# ESP32_VGA_Pocket.net
KiCad netlist of a schematic drawn in EAGLE
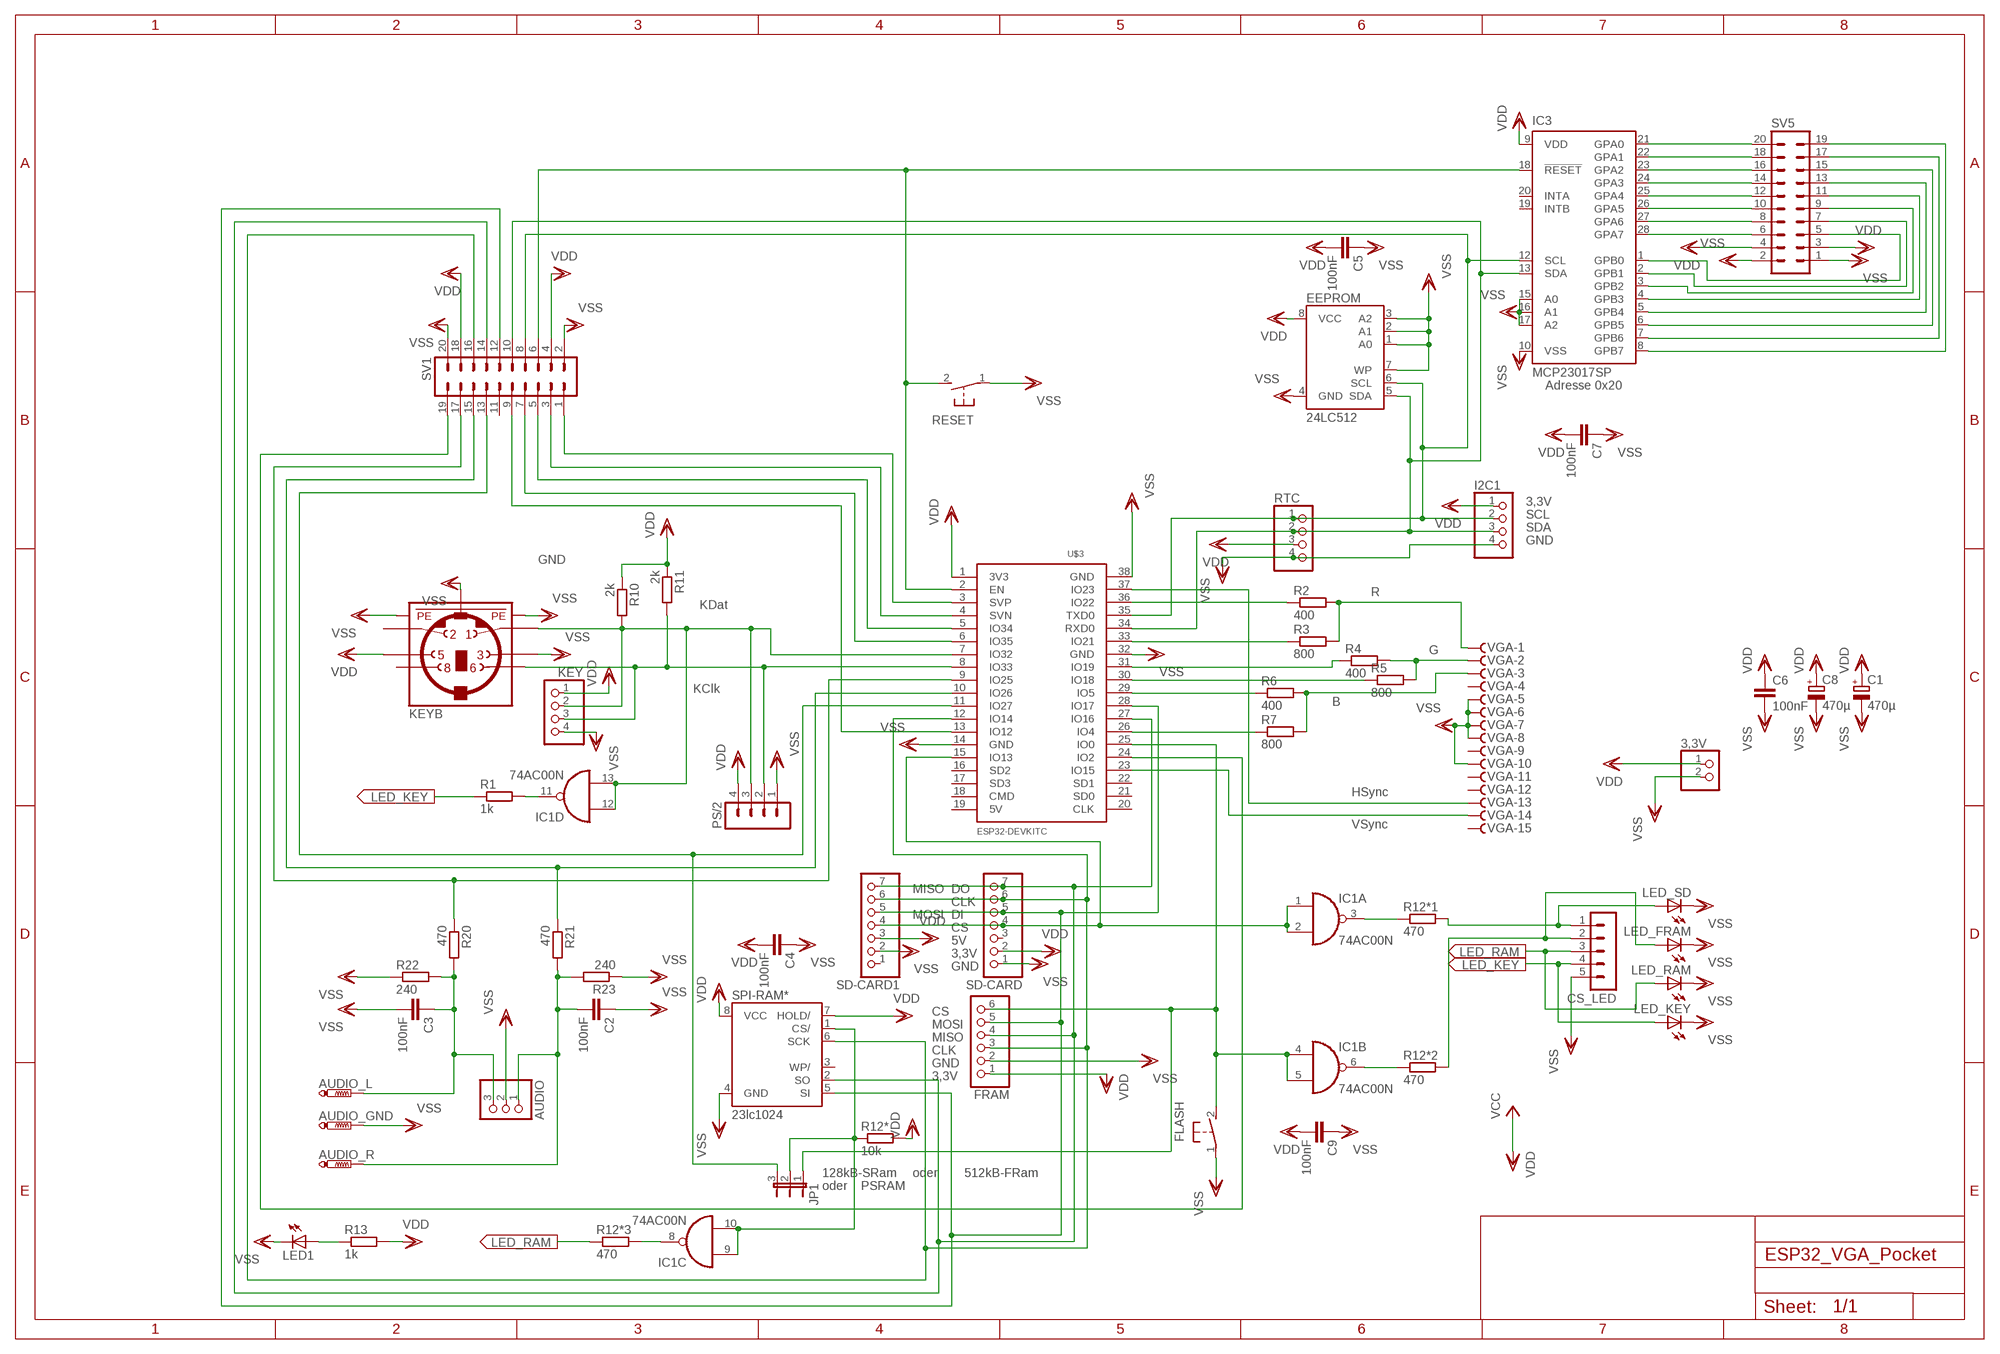
[diagram p0: schematic, sheet 1]

(export (version "E")
  (design (tool "Eeschema 10.0.6"))
  (components
    (comp (ref "3,3V")
      (value "PINHD-1X2")
      (footprint "eagle-import:1X02")
      (libsource (lib "eagle-import") (part "PINHD-1X2"))
    )
    (comp (ref "AUDIO")
      (value "PINHD-1X3")
      (footprint "eagle-import:1X03")
      (libsource (lib "eagle-import") (part "PINHD-1X3"))
    )
    (comp (ref "AUDIO_GND")
      (value "PTR1PAD1-13Y")
      (footprint "eagle-import:P1-13Y")
      (libsource (lib "eagle-import") (part "PTR1PAD1-13Y"))
    )
    (comp (ref "AUDIO_L")
      (value "PTR1PAD1-13Y")
      (footprint "eagle-import:P1-13Y")
      (libsource (lib "eagle-import") (part "PTR1PAD1-13Y"))
    )
    (comp (ref "AUDIO_R")
      (value "PTR1PAD1-13Y")
      (footprint "eagle-import:P1-13Y")
      (libsource (lib "eagle-import") (part "PTR1PAD1-13Y"))
    )
    (comp (ref "C1")
      (value "470µ")
      (footprint "eagle-import:E3,5-10")
      (libsource (lib "eagle-import") (part "CPOL-EUE3.5-10"))
    )
    (comp (ref "C2")
      (value "100nF")
      (footprint "eagle-import:C025-030X050")
      (libsource (lib "eagle-import") (part "C-EU025-030X050"))
    )
    (comp (ref "C3")
      (value "100nF")
      (footprint "eagle-import:C025-030X050")
      (libsource (lib "eagle-import") (part "C-EU025-030X050"))
    )
    (comp (ref "C4")
      (value "100nF")
      (footprint "eagle-import:C025-030X050")
      (libsource (lib "eagle-import") (part "C-EU025-030X050"))
    )
    (comp (ref "C5")
      (value "100nF")
      (footprint "eagle-import:C025-030X050")
      (libsource (lib "eagle-import") (part "C-EU025-030X050"))
    )
    (comp (ref "C6")
      (value "100nF")
      (footprint "eagle-import:C025-030X050")
      (libsource (lib "eagle-import") (part "C-EU025-030X050"))
    )
    (comp (ref "C7")
      (value "100nF")
      (footprint "eagle-import:C025-030X050")
      (libsource (lib "eagle-import") (part "C-EU025-030X050"))
    )
    (comp (ref "C8")
      (value "470µ")
      (footprint "eagle-import:E3,5-10")
      (libsource (lib "eagle-import") (part "CPOL-EUE3.5-10"))
    )
    (comp (ref "C9")
      (value "100nF")
      (footprint "eagle-import:C025-030X050")
      (libsource (lib "eagle-import") (part "C-EU025-030X050"))
    )
    (comp (ref "CS_LED")
      (value "MA05-1")
      (footprint "eagle-import:MA05-1")
      (libsource (lib "eagle-import") (part "MA05-1"))
    )
    (comp (ref "EEPROM")
      (value "24LC512")
      (footprint "eagle-import:DIL08")
      (fields (field (name "MPN") "AT24C1024BW-SH-B"))
      (libsource (lib "eagle-import") (part "AT24CP"))
    )
    (comp (ref "FLASH")
      (value "31-XX")
      (footprint "eagle-import:B3F-31XX")
      (fields
        (field (name "MPN") "B3F-3100")
        (field (name "MPN_1") "B3F-3100")
        (field (name "OC_FARNELL") "959704")
        (field (name "OC_NEWARK") "36M3582")
      )
      (libsource (lib "eagle-import") (part "31-XX"))
    )
    (comp (ref "FRAM")
      (value "PINHD-1X6")
      (footprint "eagle-import:1X06")
      (libsource (lib "eagle-import") (part "PINHD-1X6"))
    )
    (comp (ref "I2C1")
      (value "PINHD-1X4")
      (footprint "eagle-import:1X04")
      (libsource (lib "eagle-import") (part "PINHD-1X4"))
    )
    (comp (ref "IC1")
      (value "74AC00N")
      (footprint "eagle-import:DIL14")
      (libsource (lib "eagle-import") (part "7400NAC"))
    )
    (comp (ref "IC3")
      (value "MCP23017SP")
      (footprint "eagle-import:DIL28-3")
      (fields
        (field (name "MF") "MICROCHIP")
        (field (name "MPN") "MCP23017-E/SP")
        (field (name "MPN_1") "MCP23017-E/SO")
        (field (name "OC_FARNELL") "1332087")
        (field (name "OC_NEWARK") "31K2958")
      )
      (libsource (lib "eagle-import") (part "MCP23017SP"))
    )
    (comp (ref "JP1")
      (value "JP2E")
      (footprint "eagle-import:JP2")
      (libsource (lib "eagle-import") (part "JP2E"))
    )
    (comp (ref "KEY")
      (value "PINHD-1X4")
      (footprint "eagle-import:1X04")
      (libsource (lib "eagle-import") (part "PINHD-1X4"))
    )
    (comp (ref "KEYB")
      (value "MINI_DIN_6")
      (footprint "eagle-import:M_DIN6")
      (libsource (lib "eagle-import") (part "MINI_DIN_6"))
    )
    (comp (ref "LED1")
      (value "LED5MM")
      (footprint "eagle-import:LED5MM")
      (libsource (lib "eagle-import") (part "LED5MM"))
    )
    (comp (ref "LED_FRAM")
      (value "LED5MM")
      (footprint "eagle-import:LED5MM")
      (libsource (lib "eagle-import") (part "LED5MM"))
    )
    (comp (ref "LED_KEY")
      (value "LED5MM")
      (footprint "eagle-import:LED5MM")
      (libsource (lib "eagle-import") (part "LED5MM"))
    )
    (comp (ref "LED_RAM")
      (value "LED5MM")
      (footprint "eagle-import:LED5MM")
      (libsource (lib "eagle-import") (part "LED5MM"))
    )
    (comp (ref "LED_SD")
      (value "LED5MM")
      (footprint "eagle-import:LED5MM")
      (libsource (lib "eagle-import") (part "LED5MM"))
    )
    (comp (ref "PS/2")
      (value "MA04-1")
      (footprint "eagle-import:MA04-1")
      (libsource (lib "eagle-import") (part "MA04-1"))
    )
    (comp (ref "R1")
      (value "1k")
      (footprint "eagle-import:0204_7")
      (libsource (lib "eagle-import") (part "R-EU_0204/7"))
    )
    (comp (ref "R2")
      (value "400")
      (footprint "eagle-import:0204_7")
      (libsource (lib "eagle-import") (part "R-EU_0204/7"))
    )
    (comp (ref "R3")
      (value "800")
      (footprint "eagle-import:0204_7")
      (libsource (lib "eagle-import") (part "R-EU_0204/7"))
    )
    (comp (ref "R4")
      (value "400")
      (footprint "eagle-import:0204_7")
      (libsource (lib "eagle-import") (part "R-EU_0204/7"))
    )
    (comp (ref "R5")
      (value "800")
      (footprint "eagle-import:0204_7")
      (libsource (lib "eagle-import") (part "R-EU_0204/7"))
    )
    (comp (ref "R6")
      (value "400")
      (footprint "eagle-import:0204_7")
      (libsource (lib "eagle-import") (part "R-EU_0204/7"))
    )
    (comp (ref "R7")
      (value "800")
      (footprint "eagle-import:0204_7")
      (libsource (lib "eagle-import") (part "R-EU_0204/7"))
    )
    (comp (ref "R10")
      (value "2k")
      (footprint "eagle-import:0204_7")
      (libsource (lib "eagle-import") (part "R-EU_0204/7"))
    )
    (comp (ref "R11")
      (value "2k")
      (footprint "eagle-import:0204_7")
      (libsource (lib "eagle-import") (part "R-EU_0204/7"))
    )
    (comp (ref "R12*")
      (value "10k")
      (footprint "eagle-import:0204_7")
      (libsource (lib "eagle-import") (part "R-EU_0204/7"))
    )
    (comp (ref "R12*1")
      (value "470")
      (footprint "eagle-import:0204_7")
      (libsource (lib "eagle-import") (part "R-EU_0204/7"))
    )
    (comp (ref "R12*2")
      (value "470")
      (footprint "eagle-import:0204_7")
      (libsource (lib "eagle-import") (part "R-EU_0204/7"))
    )
    (comp (ref "R12*3")
      (value "470")
      (footprint "eagle-import:0204_7")
      (libsource (lib "eagle-import") (part "R-EU_0204/7"))
    )
    (comp (ref "R13")
      (value "1k")
      (footprint "eagle-import:0204_7")
      (libsource (lib "eagle-import") (part "R-EU_0204/7"))
    )
    (comp (ref "R20")
      (value "470")
      (footprint "eagle-import:0204_7")
      (libsource (lib "eagle-import") (part "R-EU_0204/7"))
    )
    (comp (ref "R21")
      (value "470")
      (footprint "eagle-import:0204_7")
      (libsource (lib "eagle-import") (part "R-EU_0204/7"))
    )
    (comp (ref "R22")
      (value "240")
      (footprint "eagle-import:0204_7")
      (libsource (lib "eagle-import") (part "R-EU_0204/7"))
    )
    (comp (ref "R23")
      (value "240")
      (footprint "eagle-import:0204_7")
      (libsource (lib "eagle-import") (part "R-EU_0204/7"))
    )
    (comp (ref "RESET")
      (value "31-XX")
      (footprint "eagle-import:B3F-31XX")
      (fields (field (name "MPN") "B3F-3100"))
      (libsource (lib "eagle-import") (part "31-XX"))
    )
    (comp (ref "RTC")
      (value "PINHD-1X4")
      (footprint "eagle-import:1X04")
      (libsource (lib "eagle-import") (part "PINHD-1X4"))
    )
    (comp (ref "SD-CARD")
      (value "PINHD-1X7")
      (footprint "eagle-import:1X07")
      (libsource (lib "eagle-import") (part "PINHD-1X7"))
    )
    (comp (ref "SD-CARD1")
      (value "PINHD-1X7")
      (footprint "eagle-import:1X07")
      (libsource (lib "eagle-import") (part "PINHD-1X7"))
    )
    (comp (ref "SPI-RAM*")
      (value "23lc1024")
      (footprint "eagle-import:DIL08")
      (fields (field (name "MPN") "CAT25040LI-G"))
      (libsource (lib "eagle-import") (part "AT25P"))
    )
    (comp (ref "SV1")
      (value "MA10-2")
      (footprint "eagle-import:MA10-2")
      (libsource (lib "eagle-import") (part "MA10-2"))
    )
    (comp (ref "SV5")
      (value "MA10-2")
      (footprint "eagle-import:MA10-2")
      (libsource (lib "eagle-import") (part "MA10-2"))
    )
    (comp (ref "U$3")
      (value "ESP32DEVKITC")
      (footprint "eagle-import:ESP32-DEVKITC")
      (libsource (lib "eagle-import") (part "ESP32DEVKITC"))
    )
    (comp (ref "VGA")
      (value "F15HDHS")
      (footprint "eagle-import:HDF15H")
      (libsource (lib "eagle-import") (part "F15?SHDH"))
    )
  )
  (nets
    (net (code "1") (name "/LED_KEY") (class "Default")
      (node (ref "CS_LED") (pin "4") (pinfunction "4_4") (pintype "passive"))
      (node (ref "LED_KEY") (pin "A") (pinfunction "A_A") (pintype "passive"))
      (node (ref "R1") (pin "1") (pinfunction "1_1") (pintype "passive"))
    )
    (net (code "2") (name "/LED_RAM") (class "Default")
      (node (ref "CS_LED") (pin "3") (pinfunction "3_3") (pintype "passive"))
      (node (ref "LED_RAM") (pin "A") (pinfunction "A_A") (pintype "passive"))
      (node (ref "R12*3") (pin "1") (pinfunction "1_1") (pintype "passive"))
    )
    (net (code "3") (name "Net-(AUDIO-Pad1)") (class "Default")
      (node (ref "AUDIO") (pin "1") (pinfunction "1_1") (pintype "passive"))
      (node (ref "AUDIO_R") (pin "TP") (pinfunction "TP_TP") (pintype "input"))
      (node (ref "C2") (pin "2") (pinfunction "2_2") (pintype "passive"))
      (node (ref "R21") (pin "2") (pinfunction "2_2") (pintype "passive"))
      (node (ref "R23") (pin "2") (pinfunction "2_2") (pintype "passive"))
    )
    (net (code "4") (name "Net-(AUDIO-Pad3)") (class "Default")
      (node (ref "AUDIO") (pin "3") (pinfunction "3_3") (pintype "passive"))
      (node (ref "AUDIO_L") (pin "TP") (pinfunction "TP_TP") (pintype "input"))
      (node (ref "C3") (pin "1") (pinfunction "1_1") (pintype "passive"))
      (node (ref "R20") (pin "2") (pinfunction "2_2") (pintype "passive"))
      (node (ref "R22") (pin "2") (pinfunction "2_2") (pintype "passive"))
    )
    (net (code "5") (name "Net-(CS_LED-Pad1)") (class "Default")
      (node (ref "CS_LED") (pin "1") (pinfunction "1_1") (pintype "passive"))
      (node (ref "LED_SD") (pin "A") (pinfunction "A_A") (pintype "passive"))
      (node (ref "R12*1") (pin "2") (pinfunction "2_2") (pintype "passive"))
    )
    (net (code "6") (name "Net-(CS_LED-Pad2)") (class "Default")
      (node (ref "CS_LED") (pin "2") (pinfunction "2_2") (pintype "passive"))
      (node (ref "LED_FRAM") (pin "A") (pinfunction "A_A") (pintype "passive"))
      (node (ref "R12*2") (pin "2") (pinfunction "2_2") (pintype "passive"))
    )
    (net (code "7") (name "Net-(EEPROM-SCL)") (class "Default")
      (node (ref "EEPROM") (pin "6") (pinfunction "SCL_6") (pintype "bidirectional"))
      (node (ref "I2C1") (pin "2") (pinfunction "2_2") (pintype "passive"))
      (node (ref "IC3") (pin "12") (pinfunction "SCL_12") (pintype "input"))
      (node (ref "RTC") (pin "1") (pinfunction "1_1") (pintype "passive"))
      (node (ref "SV1") (pin "8") (pinfunction "8_8") (pintype "passive"))
      (node (ref "U$3") (pin "35") (pinfunction "TXD0_35") (pintype "bidirectional"))
    )
    (net (code "8") (name "Net-(EEPROM-SDA)") (class "Default")
      (node (ref "EEPROM") (pin "5") (pinfunction "SDA_5") (pintype "bidirectional"))
      (node (ref "I2C1") (pin "3") (pinfunction "3_3") (pintype "passive"))
      (node (ref "IC3") (pin "13") (pinfunction "SDA_13") (pintype "bidirectional"))
      (node (ref "RTC") (pin "2") (pinfunction "2_2") (pintype "passive"))
      (node (ref "SV1") (pin "10") (pinfunction "10_10") (pintype "passive"))
      (node (ref "U$3") (pin "34") (pinfunction "RXD0_34") (pintype "bidirectional"))
    )
    (net (code "9") (name "Net-(FLASH-S)") (class "Default")
      (node (ref "FLASH") (pin "2") (pinfunction "S_2") (pintype "passive"))
      (node (ref "FRAM") (pin "6") (pinfunction "6_6") (pintype "passive"))
      (node (ref "IC1") (pin "4") (pinfunction "I0_4") (pintype "input"))
      (node (ref "IC1") (pin "5") (pinfunction "I1_5") (pintype "input"))
      (node (ref "JP1") (pin "1") (pinfunction "1_1") (pintype "passive"))
      (node (ref "U$3") (pin "25") (pinfunction "IO0_25") (pintype "bidirectional"))
    )
    (net (code "10") (name "Net-(IC1A-I0)") (class "Default")
      (node (ref "IC1") (pin "1") (pinfunction "I0_1") (pintype "input"))
      (node (ref "IC1") (pin "2") (pinfunction "I1_2") (pintype "input"))
      (node (ref "SD-CARD") (pin "4") (pinfunction "4_4") (pintype "passive"))
      (node (ref "SD-CARD1") (pin "4") (pinfunction "4_4") (pintype "passive"))
      (node (ref "U$3") (pin "15") (pinfunction "IO13_15") (pintype "bidirectional"))
    )
    (net (code "11") (name "Net-(IC1A-O)") (class "Default")
      (node (ref "IC1") (pin "3") (pinfunction "O_3") (pintype "output"))
      (node (ref "R12*1") (pin "1") (pinfunction "1_1") (pintype "passive"))
    )
    (net (code "12") (name "Net-(IC1B-O)") (class "Default")
      (node (ref "IC1") (pin "6") (pinfunction "O_6") (pintype "output"))
      (node (ref "R12*2") (pin "1") (pinfunction "1_1") (pintype "passive"))
    )
    (net (code "13") (name "Net-(IC1C-I0)") (class "Default")
      (node (ref "IC1") (pin "10") (pinfunction "I1_10") (pintype "input"))
      (node (ref "IC1") (pin "9") (pinfunction "I0_9") (pintype "input"))
      (node (ref "JP1") (pin "2") (pinfunction "2_2") (pintype "passive"))
      (node (ref "R12*") (pin "1") (pinfunction "1_1") (pintype "passive"))
      (node (ref "SPI-RAM*") (pin "1") (pinfunction "CS/_1") (pintype "input"))
    )
    (net (code "14") (name "Net-(IC1C-O)") (class "Default")
      (node (ref "IC1") (pin "8") (pinfunction "O_8") (pintype "output"))
      (node (ref "R12*3") (pin "2") (pinfunction "2_2") (pintype "passive"))
    )
    (net (code "15") (name "Net-(IC1D-I0)") (class "Default")
      (node (ref "IC1") (pin "12") (pinfunction "I0_12") (pintype "input"))
      (node (ref "IC1") (pin "13") (pinfunction "I1_13") (pintype "input"))
      (node (ref "KEY") (pin "2") (pinfunction "2_2") (pintype "passive"))
      (node (ref "KEYB") (pin "1") (pinfunction "1_1") (pintype "passive"))
      (node (ref "PS/2") (pin "3") (pinfunction "3_3") (pintype "passive"))
      (node (ref "R10") (pin "2") (pinfunction "2_2") (pintype "passive"))
      (node (ref "U$3") (pin "7") (pinfunction "IO32_7") (pintype "bidirectional"))
    )
    (net (code "16") (name "Net-(IC1D-O)") (class "Default")
      (node (ref "IC1") (pin "11") (pinfunction "O_11") (pintype "output"))
      (node (ref "R1") (pin "2") (pinfunction "2_2") (pintype "passive"))
    )
    (net (code "17") (name "Net-(IC3-GPA0)") (class "Default")
      (node (ref "IC3") (pin "21") (pinfunction "GPA0_21") (pintype "bidirectional"))
      (node (ref "SV5") (pin "20") (pinfunction "20_20") (pintype "passive"))
    )
    (net (code "18") (name "Net-(IC3-GPA1)") (class "Default")
      (node (ref "IC3") (pin "22") (pinfunction "GPA1_22") (pintype "bidirectional"))
      (node (ref "SV5") (pin "18") (pinfunction "18_18") (pintype "passive"))
    )
    (net (code "19") (name "Net-(IC3-GPA2)") (class "Default")
      (node (ref "IC3") (pin "23") (pinfunction "GPA2_23") (pintype "bidirectional"))
      (node (ref "SV5") (pin "16") (pinfunction "16_16") (pintype "passive"))
    )
    (net (code "20") (name "Net-(IC3-GPA3)") (class "Default")
      (node (ref "IC3") (pin "24") (pinfunction "GPA3_24") (pintype "bidirectional"))
      (node (ref "SV5") (pin "14") (pinfunction "14_14") (pintype "passive"))
    )
    (net (code "21") (name "Net-(IC3-GPA4)") (class "Default")
      (node (ref "IC3") (pin "25") (pinfunction "GPA4_25") (pintype "bidirectional"))
      (node (ref "SV5") (pin "12") (pinfunction "12_12") (pintype "passive"))
    )
    (net (code "22") (name "Net-(IC3-GPA5)") (class "Default")
      (node (ref "IC3") (pin "26") (pinfunction "GPA5_26") (pintype "bidirectional"))
      (node (ref "SV5") (pin "10") (pinfunction "10_10") (pintype "passive"))
    )
    (net (code "23") (name "Net-(IC3-GPA6)") (class "Default")
      (node (ref "IC3") (pin "27") (pinfunction "GPA6_27") (pintype "bidirectional"))
      (node (ref "SV5") (pin "8") (pinfunction "8_8") (pintype "passive"))
    )
    (net (code "24") (name "Net-(IC3-GPA7)") (class "Default")
      (node (ref "IC3") (pin "28") (pinfunction "GPA7_28") (pintype "bidirectional"))
      (node (ref "SV5") (pin "6") (pinfunction "6_6") (pintype "passive"))
    )
    (net (code "25") (name "Net-(IC3-GPB0)") (class "Default")
      (node (ref "IC3") (pin "1") (pinfunction "GPB0_1") (pintype "bidirectional"))
      (node (ref "SV5") (pin "5") (pinfunction "5_5") (pintype "passive"))
    )
    (net (code "26") (name "Net-(IC3-GPB1)") (class "Default")
      (node (ref "IC3") (pin "2") (pinfunction "GPB1_2") (pintype "bidirectional"))
      (node (ref "SV5") (pin "7") (pinfunction "7_7") (pintype "passive"))
    )
    (net (code "27") (name "Net-(IC3-GPB2)") (class "Default")
      (node (ref "IC3") (pin "3") (pinfunction "GPB2_3") (pintype "bidirectional"))
      (node (ref "SV5") (pin "9") (pinfunction "9_9") (pintype "passive"))
    )
    (net (code "28") (name "Net-(IC3-GPB3)") (class "Default")
      (node (ref "IC3") (pin "4") (pinfunction "GPB3_4") (pintype "bidirectional"))
      (node (ref "SV5") (pin "11") (pinfunction "11_11") (pintype "passive"))
    )
    (net (code "29") (name "Net-(IC3-GPB4)") (class "Default")
      (node (ref "IC3") (pin "5") (pinfunction "GPB4_5") (pintype "bidirectional"))
      (node (ref "SV5") (pin "13") (pinfunction "13_13") (pintype "passive"))
    )
    (net (code "30") (name "Net-(IC3-GPB5)") (class "Default")
      (node (ref "IC3") (pin "6") (pinfunction "GPB5_6") (pintype "bidirectional"))
      (node (ref "SV5") (pin "15") (pinfunction "15_15") (pintype "passive"))
    )
    (net (code "31") (name "Net-(IC3-GPB6)") (class "Default")
      (node (ref "IC3") (pin "7") (pinfunction "GPB6_7") (pintype "bidirectional"))
      (node (ref "SV5") (pin "17") (pinfunction "17_17") (pintype "passive"))
    )
    (net (code "32") (name "Net-(IC3-GPB7)") (class "Default")
      (node (ref "IC3") (pin "8") (pinfunction "GPB7_8") (pintype "bidirectional"))
      (node (ref "SV5") (pin "19") (pinfunction "19_19") (pintype "passive"))
    )
    (net (code "33") (name "Net-(IC3-~{RESET})") (class "Default")
      (node (ref "IC3") (pin "18") (pinfunction "~{RESET}_18") (pintype "input"))
      (node (ref "RESET") (pin "2") (pinfunction "S_2") (pintype "passive"))
      (node (ref "SV1") (pin "6") (pinfunction "6_6") (pintype "passive"))
      (node (ref "U$3") (pin "2") (pinfunction "EN_2") (pintype "bidirectional"))
    )
    (net (code "34") (name "Net-(LED1-PadA)") (class "Default")
      (node (ref "LED1") (pin "A") (pinfunction "A_A") (pintype "passive"))
      (node (ref "R13") (pin "1") (pinfunction "1_1") (pintype "passive"))
    )
    (net (code "35") (name "Net-(SPI-RAM*-SCK)") (class "Default")
      (node (ref "FRAM") (pin "3") (pinfunction "3_3") (pintype "passive"))
      (node (ref "SD-CARD") (pin "6") (pinfunction "6_6") (pintype "passive"))
      (node (ref "SD-CARD1") (pin "6") (pinfunction "6_6") (pintype "passive"))
      (node (ref "SPI-RAM*") (pin "6") (pinfunction "SCK_6") (pintype "bidirectional"))
      (node (ref "SV1") (pin "16") (pinfunction "16_16") (pintype "passive"))
      (node (ref "U$3") (pin "12") (pinfunction "IO14_12") (pintype "bidirectional"))
    )
    (net (code "36") (name "Net-(SPI-RAM*-SI)") (class "Default")
      (node (ref "FRAM") (pin "5") (pinfunction "5_5") (pintype "passive"))
      (node (ref "SD-CARD") (pin "5") (pinfunction "5_5") (pintype "passive"))
      (node (ref "SD-CARD1") (pin "5") (pinfunction "5_5") (pintype "passive"))
      (node (ref "SPI-RAM*") (pin "5") (pinfunction "SI_5") (pintype "bidirectional"))
      (node (ref "SV1") (pin "12") (pinfunction "12_12") (pintype "passive"))
      (node (ref "U$3") (pin "28") (pinfunction "IO17_28") (pintype "bidirectional"))
    )
    (net (code "37") (name "Net-(SPI-RAM*-SO)") (class "Default")
      (node (ref "FRAM") (pin "4") (pinfunction "4_4") (pintype "passive"))
      (node (ref "SD-CARD") (pin "7") (pinfunction "7_7") (pintype "passive"))
      (node (ref "SD-CARD1") (pin "7") (pinfunction "7_7") (pintype "passive"))
      (node (ref "SPI-RAM*") (pin "2") (pinfunction "SO_2") (pintype "input"))
      (node (ref "SV1") (pin "14") (pinfunction "14_14") (pintype "passive"))
      (node (ref "U$3") (pin "27") (pinfunction "IO16_27") (pintype "bidirectional"))
    )
    (net (code "38") (name "Net-(U$3-IO2)") (class "Default")
      (node (ref "SV1") (pin "19") (pinfunction "19_19") (pintype "passive"))
      (node (ref "U$3") (pin "24") (pinfunction "IO2_24") (pintype "bidirectional"))
    )
    (net (code "39") (name "Net-(U$3-IO4)") (class "Default")
      (node (ref "R7") (pin "1") (pinfunction "1_1") (pintype "passive"))
      (node (ref "U$3") (pin "26") (pinfunction "IO4_26") (pintype "bidirectional"))
    )
    (net (code "40") (name "Net-(U$3-IO5)") (class "Default")
      (node (ref "R6") (pin "1") (pinfunction "1_1") (pintype "passive"))
      (node (ref "U$3") (pin "29") (pinfunction "IO5_29") (pintype "bidirectional"))
    )
    (net (code "41") (name "Net-(U$3-IO12)") (class "Default")
      (node (ref "SV1") (pin "9") (pinfunction "9_9") (pintype "passive"))
      (node (ref "U$3") (pin "13") (pinfunction "IO12_13") (pintype "bidirectional"))
    )
    (net (code "42") (name "Net-(U$3-IO15)") (class "Default")
      (node (ref "U$3") (pin "23") (pinfunction "IO15_23") (pintype "bidirectional"))
      (node (ref "VGA") (pin "14") (pinfunction "F_14") (pintype "passive"))
    )
    (net (code "43") (name "Net-(U$3-IO18)") (class "Default")
      (node (ref "R5") (pin "1") (pinfunction "1_1") (pintype "passive"))
      (node (ref "U$3") (pin "30") (pinfunction "IO18_30") (pintype "bidirectional"))
    )
    (net (code "44") (name "Net-(U$3-IO19)") (class "Default")
      (node (ref "R4") (pin "1") (pinfunction "1_1") (pintype "passive"))
      (node (ref "U$3") (pin "31") (pinfunction "IO19_31") (pintype "bidirectional"))
    )
    (net (code "45") (name "Net-(U$3-IO21)") (class "Default")
      (node (ref "R3") (pin "1") (pinfunction "1_1") (pintype "passive"))
      (node (ref "U$3") (pin "33") (pinfunction "IO21_33") (pintype "bidirectional"))
    )
    (net (code "46") (name "Net-(U$3-IO22)") (class "Default")
      (node (ref "R2") (pin "1") (pinfunction "1_1") (pintype "passive"))
      (node (ref "U$3") (pin "36") (pinfunction "IO22_36") (pintype "bidirectional"))
    )
    (net (code "47") (name "Net-(U$3-IO23)") (class "Default")
      (node (ref "U$3") (pin "37") (pinfunction "IO23_37") (pintype "bidirectional"))
      (node (ref "VGA") (pin "13") (pinfunction "F_13") (pintype "passive"))
    )
    (net (code "48") (name "Net-(U$3-IO25)") (class "Default")
      (node (ref "R20") (pin "1") (pinfunction "1_1") (pintype "passive"))
      (node (ref "SV1") (pin "17") (pinfunction "17_17") (pintype "passive"))
      (node (ref "U$3") (pin "9") (pinfunction "IO25_9") (pintype "bidirectional"))
    )
    (net (code "49") (name "Net-(U$3-IO26)") (class "Default")
      (node (ref "R21") (pin "1") (pinfunction "1_1") (pintype "passive"))
      (node (ref "SV1") (pin "15") (pinfunction "15_15") (pintype "passive"))
      (node (ref "U$3") (pin "10") (pinfunction "IO26_10") (pintype "bidirectional"))
    )
    (net (code "50") (name "Net-(U$3-IO27)") (class "Default")
      (node (ref "JP1") (pin "3") (pinfunction "3_3") (pintype "passive"))
      (node (ref "SV1") (pin "13") (pinfunction "13_13") (pintype "passive"))
      (node (ref "U$3") (pin "11") (pinfunction "IO27_11") (pintype "bidirectional"))
    )
    (net (code "51") (name "Net-(U$3-IO33)") (class "Default")
      (node (ref "KEY") (pin "3") (pinfunction "3_3") (pintype "passive"))
      (node (ref "KEYB") (pin "6") (pinfunction "6_6") (pintype "passive"))
      (node (ref "PS/2") (pin "2") (pinfunction "2_2") (pintype "passive"))
      (node (ref "R11") (pin "2") (pinfunction "2_2") (pintype "passive"))
      (node (ref "U$3") (pin "8") (pinfunction "IO33_8") (pintype "bidirectional"))
    )
    (net (code "52") (name "Net-(U$3-IO34)") (class "Default")
      (node (ref "SV1") (pin "5") (pinfunction "5_5") (pintype "passive"))
      (node (ref "U$3") (pin "5") (pinfunction "IO34_5") (pintype "bidirectional"))
    )
    (net (code "53") (name "Net-(U$3-IO35)") (class "Default")
      (node (ref "SV1") (pin "7") (pinfunction "7_7") (pintype "passive"))
      (node (ref "U$3") (pin "6") (pinfunction "IO35_6") (pintype "bidirectional"))
    )
    (net (code "54") (name "Net-(U$3-SVN)") (class "Default")
      (node (ref "SV1") (pin "3") (pinfunction "3_3") (pintype "passive"))
      (node (ref "U$3") (pin "4") (pinfunction "SVN_4") (pintype "bidirectional"))
    )
    (net (code "55") (name "Net-(U$3-SVP)") (class "Default")
      (node (ref "SV1") (pin "1") (pinfunction "1_1") (pintype "passive"))
      (node (ref "U$3") (pin "3") (pinfunction "SVP_3") (pintype "bidirectional"))
    )
    (net (code "56") (name "Net-(VGAA-F)") (class "Default")
      (node (ref "R2") (pin "2") (pinfunction "2_2") (pintype "passive"))
      (node (ref "R3") (pin "2") (pinfunction "2_2") (pintype "passive"))
      (node (ref "VGA") (pin "1") (pinfunction "F_1") (pintype "passive"))
    )
    (net (code "57") (name "Net-(VGAH-F)") (class "Default")
      (node (ref "R4") (pin "2") (pinfunction "2_2") (pintype "passive"))
      (node (ref "R5") (pin "2") (pinfunction "2_2") (pintype "passive"))
      (node (ref "VGA") (pin "2") (pinfunction "F_2") (pintype "passive"))
    )
    (net (code "58") (name "Net-(VGAI-F)") (class "Default")
      (node (ref "R6") (pin "2") (pinfunction "2_2") (pintype "passive"))
      (node (ref "R7") (pin "2") (pinfunction "2_2") (pintype "passive"))
      (node (ref "VGA") (pin "3") (pinfunction "F_3") (pintype "passive"))
    )
    (net (code "59") (name "VCC") (class "Default")
      (node (ref "3,3V") (pin "1") (pinfunction "1_1") (pintype "passive"))
      (node (ref "C1") (pin "+") (pinfunction "+_+") (pintype "passive"))
      (node (ref "C4") (pin "2") (pinfunction "2_2") (pintype "passive"))
      (node (ref "C5") (pin "2") (pinfunction "2_2") (pintype "passive"))
      (node (ref "C6") (pin "1") (pinfunction "1_1") (pintype "passive"))
      (node (ref "C7") (pin "2") (pinfunction "2_2") (pintype "passive"))
      (node (ref "C8") (pin "+") (pinfunction "+_+") (pintype "passive"))
      (node (ref "C9") (pin "2") (pinfunction "2_2") (pintype "passive"))
      (node (ref "EEPROM") (pin "8") (pinfunction "VCC_8") (pintype "power_in"))
      (node (ref "FRAM") (pin "1") (pinfunction "1_1") (pintype "passive"))
      (node (ref "I2C1") (pin "1") (pinfunction "1_1") (pintype "passive"))
      (node (ref "IC3") (pin "9") (pinfunction "VDD_9") (pintype "power_in"))
      (node (ref "KEY") (pin "1") (pinfunction "1_1") (pintype "passive"))
      (node (ref "KEYB") (pin "5") (pinfunction "5_5") (pintype "passive"))
      (node (ref "PS/2") (pin "4") (pinfunction "4_4") (pintype "passive"))
      (node (ref "R10") (pin "1") (pinfunction "1_1") (pintype "passive"))
      (node (ref "R11") (pin "1") (pinfunction "1_1") (pintype "passive"))
      (node (ref "R12*") (pin "2") (pinfunction "2_2") (pintype "passive"))
      (node (ref "R13") (pin "2") (pinfunction "2_2") (pintype "passive"))
      (node (ref "RTC") (pin "3") (pinfunction "3_3") (pintype "passive"))
      (node (ref "SD-CARD") (pin "2") (pinfunction "2_2") (pintype "passive"))
      (node (ref "SD-CARD1") (pin "3") (pinfunction "3_3") (pintype "passive"))
      (node (ref "SPI-RAM*") (pin "7") (pinfunction "HOLD/_7") (pintype "input"))
      (node (ref "SPI-RAM*") (pin "8") (pinfunction "VCC_8") (pintype "power_in"))
      (node (ref "SV1") (pin "18") (pinfunction "18_18") (pintype "passive"))
      (node (ref "SV1") (pin "4") (pinfunction "4_4") (pintype "passive"))
      (node (ref "SV5") (pin "3") (pinfunction "3_3") (pintype "passive"))
      (node (ref "SV5") (pin "4") (pinfunction "4_4") (pintype "passive"))
      (node (ref "U$3") (pin "1") (pinfunction "3V3_1") (pintype "bidirectional"))
    )
    (net (code "60") (name "VSS") (class "Default")
      (node (ref "3,3V") (pin "2") (pinfunction "2_2") (pintype "passive"))
      (node (ref "AUDIO") (pin "2") (pinfunction "2_2") (pintype "passive"))
      (node (ref "AUDIO_GND") (pin "TP") (pinfunction "TP_TP") (pintype "input"))
      (node (ref "C1") (pin "-") (pinfunction "-_-") (pintype "passive"))
      (node (ref "C2") (pin "1") (pinfunction "1_1") (pintype "passive"))
      (node (ref "C3") (pin "2") (pinfunction "2_2") (pintype "passive"))
      (node (ref "C4") (pin "1") (pinfunction "1_1") (pintype "passive"))
      (node (ref "C5") (pin "1") (pinfunction "1_1") (pintype "passive"))
      (node (ref "C6") (pin "2") (pinfunction "2_2") (pintype "passive"))
      (node (ref "C7") (pin "1") (pinfunction "1_1") (pintype "passive"))
      (node (ref "C8") (pin "-") (pinfunction "-_-") (pintype "passive"))
      (node (ref "C9") (pin "1") (pinfunction "1_1") (pintype "passive"))
      (node (ref "CS_LED") (pin "5") (pinfunction "5_5") (pintype "passive"))
      (node (ref "EEPROM") (pin "1") (pinfunction "A0_1") (pintype "input"))
      (node (ref "EEPROM") (pin "2") (pinfunction "A1_2") (pintype "input"))
      (node (ref "EEPROM") (pin "3") (pinfunction "A2_3") (pintype "input"))
      (node (ref "EEPROM") (pin "4") (pinfunction "GND_4") (pintype "power_in"))
      (node (ref "EEPROM") (pin "7") (pinfunction "WP_7") (pintype "input"))
      (node (ref "FLASH") (pin "1") (pinfunction "P_1") (pintype "passive"))
      (node (ref "FRAM") (pin "2") (pinfunction "2_2") (pintype "passive"))
      (node (ref "I2C1") (pin "4") (pinfunction "4_4") (pintype "passive"))
      (node (ref "IC3") (pin "10") (pinfunction "VSS_10") (pintype "power_in"))
      (node (ref "IC3") (pin "15") (pinfunction "A0_15") (pintype "input"))
      (node (ref "IC3") (pin "16") (pinfunction "A1_16") (pintype "input"))
      (node (ref "IC3") (pin "17") (pinfunction "A2_17") (pintype "input"))
      (node (ref "KEY") (pin "4") (pinfunction "4_4") (pintype "passive"))
      (node (ref "KEYB") (pin "3") (pinfunction "3_3") (pintype "passive"))
      (node (ref "KEYB") (pin "SH1") (pinfunction "PE1_SH1") (pintype "power_in"))
      (node (ref "KEYB") (pin "SH2") (pinfunction "PE2_SH2") (pintype "power_in"))
      (node (ref "KEYB") (pin "SH3") (pinfunction "PE3_SH3") (pintype "power_in"))
      (node (ref "LED1") (pin "K") (pinfunction "C_K") (pintype "passive"))
      (node (ref "LED_FRAM") (pin "K") (pinfunction "C_K") (pintype "passive"))
      (node (ref "LED_KEY") (pin "K") (pinfunction "C_K") (pintype "passive"))
      (node (ref "LED_RAM") (pin "K") (pinfunction "C_K") (pintype "passive"))
      (node (ref "LED_SD") (pin "K") (pinfunction "C_K") (pintype "passive"))
      (node (ref "PS/2") (pin "1") (pinfunction "1_1") (pintype "passive"))
      (node (ref "R22") (pin "1") (pinfunction "1_1") (pintype "passive"))
      (node (ref "R23") (pin "1") (pinfunction "1_1") (pintype "passive"))
      (node (ref "RESET") (pin "1") (pinfunction "P_1") (pintype "passive"))
      (node (ref "RTC") (pin "4") (pinfunction "4_4") (pintype "passive"))
      (node (ref "SD-CARD") (pin "1") (pinfunction "1_1") (pintype "passive"))
      (node (ref "SD-CARD1") (pin "2") (pinfunction "2_2") (pintype "passive"))
      (node (ref "SPI-RAM*") (pin "4") (pinfunction "GND_4") (pintype "power_in"))
      (node (ref "SV1") (pin "2") (pinfunction "2_2") (pintype "passive"))
      (node (ref "SV1") (pin "20") (pinfunction "20_20") (pintype "passive"))
      (node (ref "SV5") (pin "1") (pinfunction "1_1") (pintype "passive"))
      (node (ref "SV5") (pin "2") (pinfunction "2_2") (pintype "passive"))
      (node (ref "U$3") (pin "14") (pinfunction "GND_14") (pintype "bidirectional"))
      (node (ref "U$3") (pin "32") (pinfunction "GND_32") (pintype "bidirectional"))
      (node (ref "U$3") (pin "38") (pinfunction "GND_38") (pintype "bidirectional"))
      (node (ref "VGA") (pin "10") (pinfunction "F_10") (pintype "passive"))
      (node (ref "VGA") (pin "5") (pinfunction "F_5") (pintype "passive"))
      (node (ref "VGA") (pin "6") (pinfunction "F_6") (pintype "passive"))
      (node (ref "VGA") (pin "7") (pinfunction "F_7") (pintype "passive"))
      (node (ref "VGA") (pin "8") (pinfunction "F_8") (pintype "passive"))
    )
    (net (code "61") (name "unconnected-(IC3-INTA-Pad20)") (class "Default")
      (node (ref "IC3") (pin "20") (pinfunction "INTA_20") (pintype "output"))
    )
    (net (code "62") (name "unconnected-(IC3-INTB-Pad19)") (class "Default")
      (node (ref "IC3") (pin "19") (pinfunction "INTB_19") (pintype "output"))
    )
    (net (code "63") (name "unconnected-(KEYB-Pad2)") (class "Default")
      (node (ref "KEYB") (pin "2") (pinfunction "2_2") (pintype "passive"))
    )
    (net (code "64") (name "unconnected-(KEYB-Pad8)") (class "Default")
      (node (ref "KEYB") (pin "8") (pinfunction "8_8") (pintype "passive"))
    )
    (net (code "65") (name "unconnected-(SD-CARD-Pad3)") (class "Default")
      (node (ref "SD-CARD") (pin "3") (pinfunction "3_3") (pintype "passive"))
    )
    (net (code "66") (name "unconnected-(SD-CARD1-Pad1)") (class "Default")
      (node (ref "SD-CARD1") (pin "1") (pinfunction "1_1") (pintype "passive"))
    )
    (net (code "67") (name "unconnected-(SPI-RAM*-WP{slash}-Pad3)") (class "Default")
      (node (ref "SPI-RAM*") (pin "3") (pinfunction "WP/_3") (pintype "input"))
    )
    (net (code "68") (name "unconnected-(SV1-Pad11)") (class "Default")
      (node (ref "SV1") (pin "11") (pinfunction "11_11") (pintype "passive"))
    )
    (net (code "69") (name "unconnected-(U$3-5V-Pad19)") (class "Default")
      (node (ref "U$3") (pin "19") (pinfunction "5V_19") (pintype "bidirectional"))
    )
    (net (code "70") (name "unconnected-(U$3-CLK-Pad20)") (class "Default")
      (node (ref "U$3") (pin "20") (pinfunction "CLK_20") (pintype "bidirectional"))
    )
    (net (code "71") (name "unconnected-(U$3-CMD-Pad18)") (class "Default")
      (node (ref "U$3") (pin "18") (pinfunction "CMD_18") (pintype "bidirectional"))
    )
    (net (code "72") (name "unconnected-(U$3-SD0-Pad21)") (class "Default")
      (node (ref "U$3") (pin "21") (pinfunction "SD0_21") (pintype "bidirectional"))
    )
    (net (code "73") (name "unconnected-(U$3-SD1-Pad22)") (class "Default")
      (node (ref "U$3") (pin "22") (pinfunction "SD1_22") (pintype "bidirectional"))
    )
    (net (code "74") (name "unconnected-(U$3-SD2-Pad16)") (class "Default")
      (node (ref "U$3") (pin "16") (pinfunction "SD2_16") (pintype "bidirectional"))
    )
    (net (code "75") (name "unconnected-(U$3-SD3-Pad17)") (class "Default")
      (node (ref "U$3") (pin "17") (pinfunction "SD3_17") (pintype "bidirectional"))
    )
    (net (code "76") (name "unconnected-(VGAC-F-Pad11)") (class "Default")
      (node (ref "VGA") (pin "11") (pinfunction "F_11") (pintype "passive"))
    )
    (net (code "77") (name "unconnected-(VGAD-F-Pad12)") (class "Default")
      (node (ref "VGA") (pin "12") (pinfunction "F_12") (pintype "passive"))
    )
    (net (code "78") (name "unconnected-(VGAG-F-Pad15)") (class "Default")
      (node (ref "VGA") (pin "15") (pinfunction "F_15") (pintype "passive"))
    )
    (net (code "79") (name "unconnected-(VGAJ-F-Pad4)") (class "Default")
      (node (ref "VGA") (pin "4") (pinfunction "F_4") (pintype "passive"))
    )
    (net (code "80") (name "unconnected-(VGAO-F-Pad9)") (class "Default")
      (node (ref "VGA") (pin "9") (pinfunction "F_9") (pintype "passive"))
    )
  )
)
